# NPMDriver.net
KiCad netlist of a schematic drawn in EAGLE
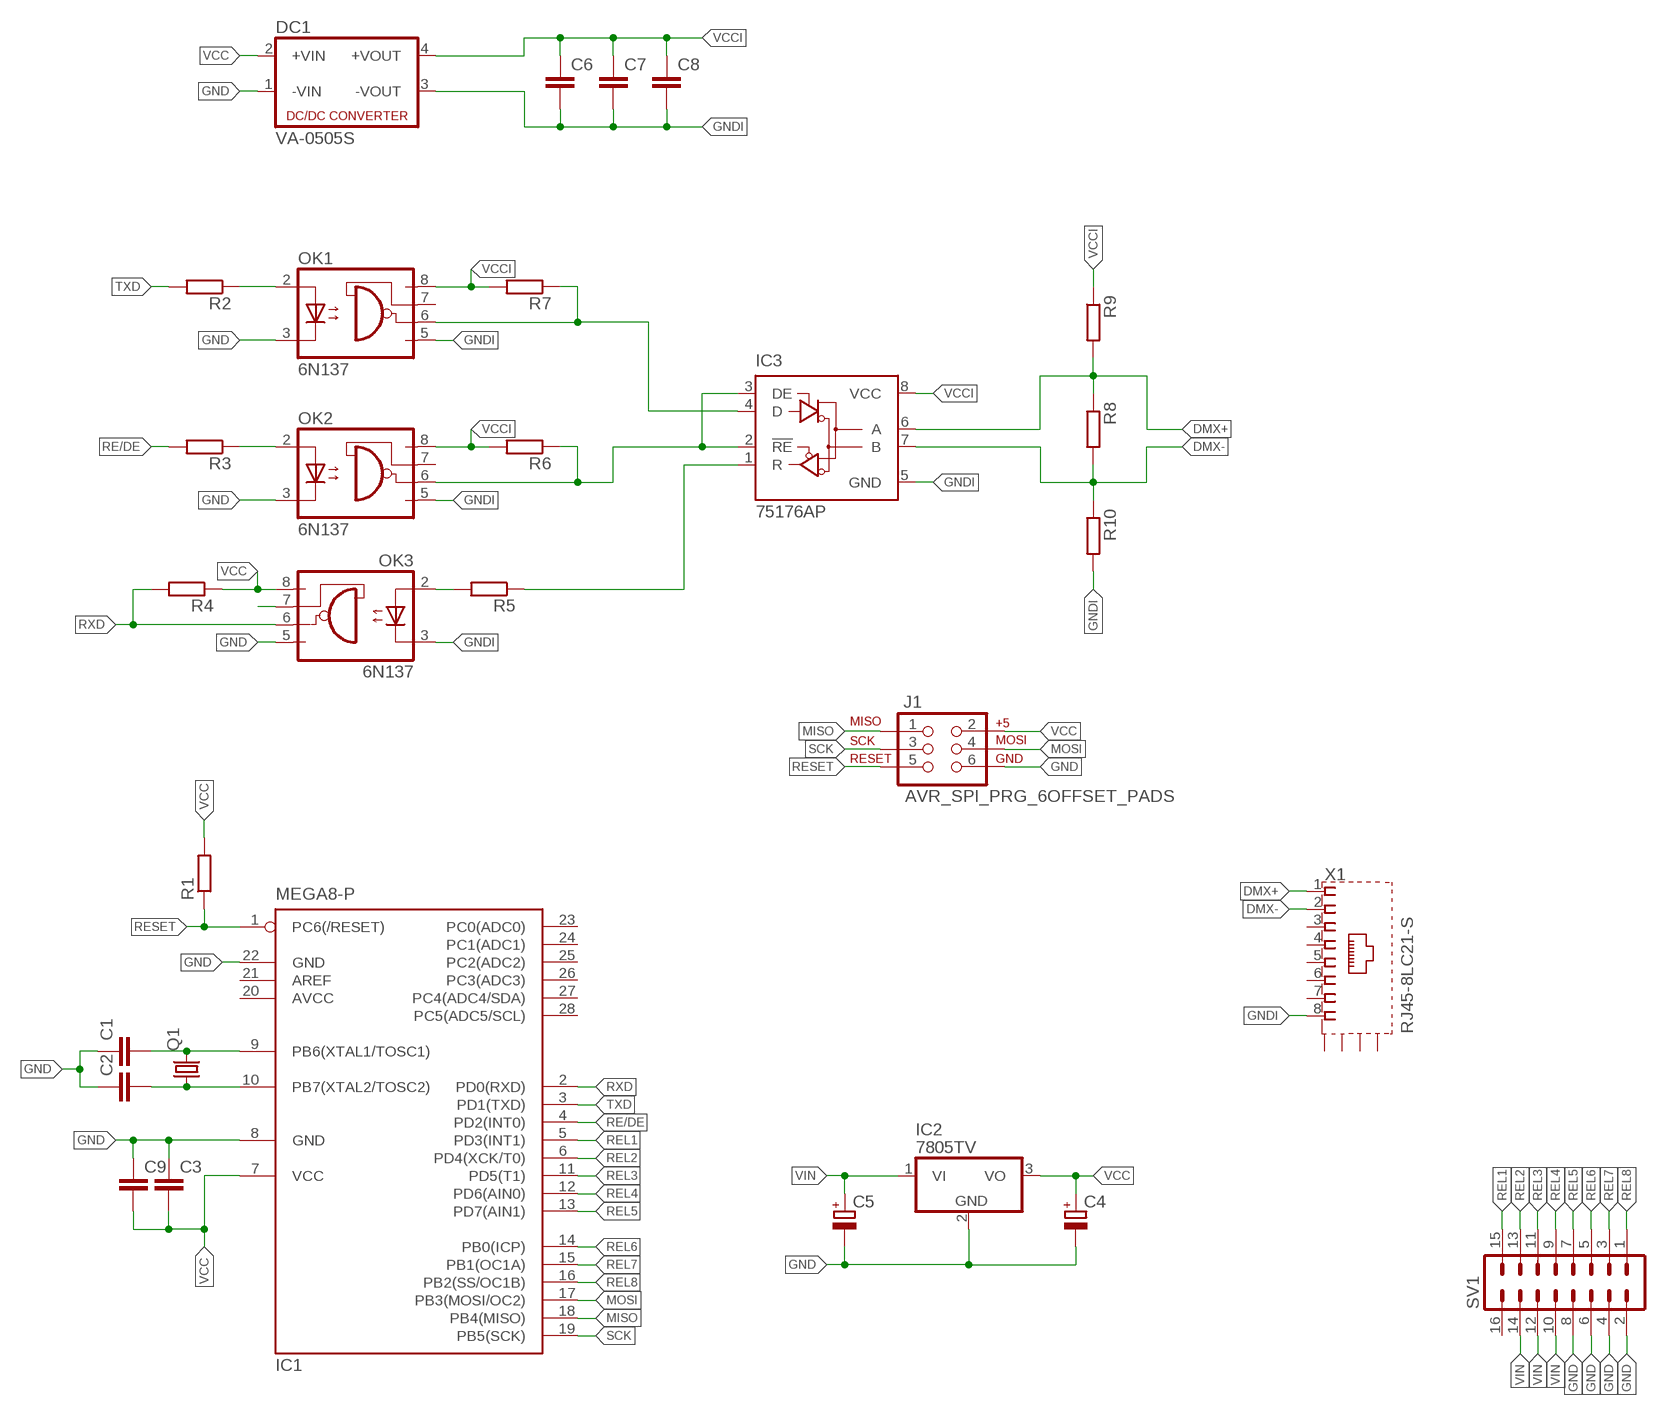
[diagram p0: schematic, sheet 1]

(export (version "E")
  (design (tool "Eeschema 10.0.6"))
  (components
    (comp (ref "C1")
      (value "C-EU025-025X050")
      (footprint "eagle-import:C025-025X050")
      (libsource (lib "eagle-import") (part "C-EU025-025X050"))
    )
    (comp (ref "C2")
      (value "C-EU025-025X050")
      (footprint "eagle-import:C025-025X050")
      (libsource (lib "eagle-import") (part "C-EU025-025X050"))
    )
    (comp (ref "C3")
      (value "C-EU050-035X075")
      (footprint "eagle-import:C050-035X075")
      (libsource (lib "eagle-import") (part "C-EU050-035X075"))
    )
    (comp (ref "C4")
      (value "CPOL-EUE5-8.5")
      (footprint "eagle-import:E5-8,5")
      (libsource (lib "eagle-import") (part "CPOL-EUE5-8.5"))
    )
    (comp (ref "C5")
      (value "CPOL-EUE5-8.5")
      (footprint "eagle-import:E5-8,5")
      (libsource (lib "eagle-import") (part "CPOL-EUE5-8.5"))
    )
    (comp (ref "C6")
      (value "C-EU050-035X075")
      (footprint "eagle-import:C050-035X075")
      (libsource (lib "eagle-import") (part "C-EU050-035X075"))
    )
    (comp (ref "C7")
      (value "C-EU050-035X075")
      (footprint "eagle-import:C050-035X075")
      (libsource (lib "eagle-import") (part "C-EU050-035X075"))
    )
    (comp (ref "C8")
      (value "C-EU050-035X075")
      (footprint "eagle-import:C050-035X075")
      (libsource (lib "eagle-import") (part "C-EU050-035X075"))
    )
    (comp (ref "C9")
      (value "C-EU050-035X075")
      (footprint "eagle-import:C050-035X075")
      (libsource (lib "eagle-import") (part "C-EU050-035X075"))
    )
    (comp (ref "DC1")
      (value "VA-0505S")
      (footprint "eagle-import:4SIL")
      (libsource (lib "eagle-import") (part "VA-?S0505"))
    )
    (comp (ref "IC1")
      (value "MEGA8-P")
      (footprint "eagle-import:DIL28-3")
      (libsource (lib "eagle-import") (part "MEGA8-P"))
    )
    (comp (ref "IC2")
      (value "7805TV")
      (footprint "eagle-import:TO220V")
      (libsource (lib "eagle-import") (part "78TV05"))
    )
    (comp (ref "IC3")
      (value "75176AP")
      (footprint "eagle-import:DIL08")
      (libsource (lib "eagle-import") (part "75176AP"))
    )
    (comp (ref "J1")
      (value "AVR_SPI_PRG_6OFFSET_PADS")
      (footprint "eagle-import:2X3_OFFSET")
      (libsource (lib "eagle-import") (part "AVR_SPI_PRG_6OFFSET_PADS"))
    )
    (comp (ref "OK1")
      (value "6N137")
      (footprint "eagle-import:DIL08")
      (libsource (lib "eagle-import") (part "6N137"))
    )
    (comp (ref "OK2")
      (value "6N137")
      (footprint "eagle-import:DIL08")
      (libsource (lib "eagle-import") (part "6N137"))
    )
    (comp (ref "OK3")
      (value "6N137")
      (footprint "eagle-import:DIL08")
      (libsource (lib "eagle-import") (part "6N137"))
    )
    (comp (ref "Q1")
      (value "CRYSTALHC49S")
      (footprint "eagle-import:HC49_S")
      (libsource (lib "eagle-import") (part "CRYSTALHC49S"))
    )
    (comp (ref "R1")
      (value "R-EU_0207/10")
      (footprint "eagle-import:0207_10")
      (libsource (lib "eagle-import") (part "R-EU_0207/10"))
    )
    (comp (ref "R2")
      (value "R-EU_0207/10")
      (footprint "eagle-import:0207_10")
      (libsource (lib "eagle-import") (part "R-EU_0207/10"))
    )
    (comp (ref "R3")
      (value "R-EU_0207/10")
      (footprint "eagle-import:0207_10")
      (libsource (lib "eagle-import") (part "R-EU_0207/10"))
    )
    (comp (ref "R4")
      (value "R-EU_0207/10")
      (footprint "eagle-import:0207_10")
      (libsource (lib "eagle-import") (part "R-EU_0207/10"))
    )
    (comp (ref "R5")
      (value "R-EU_0207/10")
      (footprint "eagle-import:0207_10")
      (libsource (lib "eagle-import") (part "R-EU_0207/10"))
    )
    (comp (ref "R6")
      (value "R-EU_0207/10")
      (footprint "eagle-import:0207_10")
      (libsource (lib "eagle-import") (part "R-EU_0207/10"))
    )
    (comp (ref "R7")
      (value "R-EU_0207/10")
      (footprint "eagle-import:0207_10")
      (libsource (lib "eagle-import") (part "R-EU_0207/10"))
    )
    (comp (ref "R8")
      (value "R-EU_0207/10")
      (footprint "eagle-import:0207_10")
      (libsource (lib "eagle-import") (part "R-EU_0207/10"))
    )
    (comp (ref "R9")
      (value "R-EU_0207/10")
      (footprint "eagle-import:0207_10")
      (libsource (lib "eagle-import") (part "R-EU_0207/10"))
    )
    (comp (ref "R10")
      (value "R-EU_0207/10")
      (footprint "eagle-import:0207_10")
      (libsource (lib "eagle-import") (part "R-EU_0207/10"))
    )
    (comp (ref "SV1")
      (value "ML163M")
      (footprint "eagle-import:3M_16")
      (libsource (lib "eagle-import") (part "ML163M"))
    )
    (comp (ref "X1")
      (value "RJ45-8LC21-S")
      (footprint "eagle-import:RJ45-SHIELD1")
      (libsource (lib "eagle-import") (part "RJ4521-S-8LC"))
    )
  )
  (nets
    (net (code "1") (name "/AVCC") (class "Default")
      (node (ref "IC1") (pin "20") (pinfunction "AVCC_20") (pintype "power_in"))
    )
    (net (code "2") (name "DMX+") (class "Default")
      (node (ref "IC3") (pin "6") (pinfunction "A_6") (pintype "output"))
      (node (ref "R8") (pin "1") (pinfunction "1_1") (pintype "passive"))
      (node (ref "R9") (pin "2") (pinfunction "2_2") (pintype "passive"))
      (node (ref "X1") (pin "1") (pinfunction "1_1") (pintype "passive"))
    )
    (net (code "3") (name "DMX-") (class "Default")
      (node (ref "IC3") (pin "7") (pinfunction "B_7") (pintype "output"))
      (node (ref "R10") (pin "1") (pinfunction "1_1") (pintype "passive"))
      (node (ref "R8") (pin "2") (pinfunction "2_2") (pintype "passive"))
      (node (ref "X1") (pin "2") (pinfunction "2_2") (pintype "passive"))
    )
    (net (code "4") (name "GND") (class "Default")
      (node (ref "C1") (pin "1") (pinfunction "1_1") (pintype "passive"))
      (node (ref "C2") (pin "1") (pinfunction "1_1") (pintype "passive"))
      (node (ref "C3") (pin "1") (pinfunction "1_1") (pintype "passive"))
      (node (ref "C4") (pin "-") (pinfunction "-_-") (pintype "passive"))
      (node (ref "C5") (pin "-") (pinfunction "-_-") (pintype "passive"))
      (node (ref "C9") (pin "1") (pinfunction "1_1") (pintype "passive"))
      (node (ref "DC1") (pin "1") (pinfunction "-VIN_1") (pintype "passive"))
      (node (ref "IC1") (pin "22") (pinfunction "GND_22") (pintype "power_in"))
      (node (ref "IC1") (pin "8") (pinfunction "GND_8") (pintype "power_in"))
      (node (ref "IC2") (pin "2") (pinfunction "GND_2") (pintype "passive"))
      (node (ref "J1") (pin "6") (pinfunction "6_6") (pintype "passive"))
      (node (ref "OK1") (pin "3") (pinfunction "C_3") (pintype "passive"))
      (node (ref "OK2") (pin "3") (pinfunction "C_3") (pintype "passive"))
      (node (ref "OK3") (pin "5") (pinfunction "GND_5") (pintype "passive"))
      (node (ref "SV1") (pin "2") (pinfunction "2_2") (pintype "passive"))
      (node (ref "SV1") (pin "4") (pinfunction "4_4") (pintype "passive"))
      (node (ref "SV1") (pin "6") (pinfunction "6_6") (pintype "passive"))
      (node (ref "SV1") (pin "8") (pinfunction "8_8") (pintype "passive"))
    )
    (net (code "5") (name "GNDI") (class "Default")
      (node (ref "C6") (pin "2") (pinfunction "2_2") (pintype "passive"))
      (node (ref "C7") (pin "2") (pinfunction "2_2") (pintype "passive"))
      (node (ref "C8") (pin "2") (pinfunction "2_2") (pintype "passive"))
      (node (ref "DC1") (pin "3") (pinfunction "-VOUT_3") (pintype "passive"))
      (node (ref "IC3") (pin "5") (pinfunction "GND_5") (pintype "power_in"))
      (node (ref "OK1") (pin "5") (pinfunction "GND_5") (pintype "passive"))
      (node (ref "OK2") (pin "5") (pinfunction "GND_5") (pintype "passive"))
      (node (ref "OK3") (pin "3") (pinfunction "C_3") (pintype "passive"))
      (node (ref "R10") (pin "2") (pinfunction "2_2") (pintype "passive"))
      (node (ref "X1") (pin "8") (pinfunction "8_8") (pintype "passive"))
    )
    (net (code "6") (name "MISO") (class "Default")
      (node (ref "IC1") (pin "18") (pinfunction "PB4(MISO)_18") (pintype "bidirectional"))
      (node (ref "J1") (pin "1") (pinfunction "1_1") (pintype "passive"))
    )
    (net (code "7") (name "MOSI") (class "Default")
      (node (ref "IC1") (pin "17") (pinfunction "PB3(MOSI/OC2)_17") (pintype "bidirectional"))
      (node (ref "J1") (pin "4") (pinfunction "4_4") (pintype "passive"))
    )
    (net (code "8") (name "Net-(IC1-PB6(XTAL1{slash}TOSC1))") (class "Default")
      (node (ref "C1") (pin "2") (pinfunction "2_2") (pintype "passive"))
      (node (ref "IC1") (pin "9") (pinfunction "PB6(XTAL1/TOSC1)_9") (pintype "bidirectional"))
      (node (ref "Q1") (pin "2") (pinfunction "2_2") (pintype "passive"))
    )
    (net (code "9") (name "Net-(IC1-PB7(XTAL2{slash}TOSC2))") (class "Default")
      (node (ref "C2") (pin "2") (pinfunction "2_2") (pintype "passive"))
      (node (ref "IC1") (pin "10") (pinfunction "PB7(XTAL2/TOSC2)_10") (pintype "bidirectional"))
      (node (ref "Q1") (pin "1") (pinfunction "1_1") (pintype "passive"))
    )
    (net (code "10") (name "Net-(IC3-D)") (class "Default")
      (node (ref "IC3") (pin "4") (pinfunction "D_4") (pintype "input"))
      (node (ref "OK1") (pin "6") (pinfunction "VO_6") (pintype "passive"))
      (node (ref "R7") (pin "1") (pinfunction "1_1") (pintype "passive"))
    )
    (net (code "11") (name "Net-(IC3-DE)") (class "Default")
      (node (ref "IC3") (pin "2") (pinfunction "~{RE}_2") (pintype "input"))
      (node (ref "IC3") (pin "3") (pinfunction "DE_3") (pintype "input"))
      (node (ref "OK2") (pin "6") (pinfunction "VO_6") (pintype "passive"))
      (node (ref "R6") (pin "1") (pinfunction "1_1") (pintype "passive"))
    )
    (net (code "12") (name "Net-(IC3-R)") (class "Default")
      (node (ref "IC3") (pin "1") (pinfunction "R_1") (pintype "input"))
      (node (ref "R5") (pin "1") (pinfunction "1_1") (pintype "passive"))
    )
    (net (code "13") (name "Net-(OK1-A)") (class "Default")
      (node (ref "OK1") (pin "2") (pinfunction "A_2") (pintype "passive"))
      (node (ref "R2") (pin "1") (pinfunction "1_1") (pintype "passive"))
    )
    (net (code "14") (name "Net-(OK2-A)") (class "Default")
      (node (ref "OK2") (pin "2") (pinfunction "A_2") (pintype "passive"))
      (node (ref "R3") (pin "1") (pinfunction "1_1") (pintype "passive"))
    )
    (net (code "15") (name "Net-(OK3-A)") (class "Default")
      (node (ref "OK3") (pin "2") (pinfunction "A_2") (pintype "passive"))
      (node (ref "R5") (pin "2") (pinfunction "2_2") (pintype "passive"))
    )
    (net (code "16") (name "REL1") (class "Default")
      (node (ref "IC1") (pin "5") (pinfunction "PD3(INT1)_5") (pintype "bidirectional"))
      (node (ref "SV1") (pin "15") (pinfunction "15_15") (pintype "passive"))
    )
    (net (code "17") (name "REL2") (class "Default")
      (node (ref "IC1") (pin "6") (pinfunction "PD4(XCK/T0)_6") (pintype "bidirectional"))
      (node (ref "SV1") (pin "13") (pinfunction "13_13") (pintype "passive"))
    )
    (net (code "18") (name "REL3") (class "Default")
      (node (ref "IC1") (pin "11") (pinfunction "PD5(T1)_11") (pintype "bidirectional"))
      (node (ref "SV1") (pin "11") (pinfunction "11_11") (pintype "passive"))
    )
    (net (code "19") (name "REL4") (class "Default")
      (node (ref "IC1") (pin "12") (pinfunction "PD6(AIN0)_12") (pintype "bidirectional"))
      (node (ref "SV1") (pin "9") (pinfunction "9_9") (pintype "passive"))
    )
    (net (code "20") (name "REL5") (class "Default")
      (node (ref "IC1") (pin "13") (pinfunction "PD7(AIN1)_13") (pintype "bidirectional"))
      (node (ref "SV1") (pin "7") (pinfunction "7_7") (pintype "passive"))
    )
    (net (code "21") (name "REL6") (class "Default")
      (node (ref "IC1") (pin "14") (pinfunction "PB0(ICP)_14") (pintype "bidirectional"))
      (node (ref "SV1") (pin "5") (pinfunction "5_5") (pintype "passive"))
    )
    (net (code "22") (name "REL7") (class "Default")
      (node (ref "IC1") (pin "15") (pinfunction "PB1(OC1A)_15") (pintype "bidirectional"))
      (node (ref "SV1") (pin "3") (pinfunction "3_3") (pintype "passive"))
    )
    (net (code "23") (name "REL8") (class "Default")
      (node (ref "IC1") (pin "16") (pinfunction "PB2(SS/OC1B)_16") (pintype "bidirectional"))
      (node (ref "SV1") (pin "1") (pinfunction "1_1") (pintype "passive"))
    )
    (net (code "24") (name "RESET") (class "Default")
      (node (ref "IC1") (pin "1") (pinfunction "PC6(/RESET)_1") (pintype "bidirectional"))
      (node (ref "J1") (pin "5") (pinfunction "5_5") (pintype "passive"))
      (node (ref "R1") (pin "1") (pinfunction "1_1") (pintype "passive"))
    )
    (net (code "25") (name "RE{slash}DE") (class "Default")
      (node (ref "IC1") (pin "4") (pinfunction "PD2(INT0)_4") (pintype "bidirectional"))
      (node (ref "R3") (pin "2") (pinfunction "2_2") (pintype "passive"))
    )
    (net (code "26") (name "RXD") (class "Default")
      (node (ref "IC1") (pin "2") (pinfunction "PD0(RXD)_2") (pintype "bidirectional"))
      (node (ref "OK3") (pin "6") (pinfunction "VO_6") (pintype "passive"))
      (node (ref "R4") (pin "2") (pinfunction "2_2") (pintype "passive"))
    )
    (net (code "27") (name "SCK") (class "Default")
      (node (ref "IC1") (pin "19") (pinfunction "PB5(SCK)_19") (pintype "bidirectional"))
      (node (ref "J1") (pin "3") (pinfunction "3_3") (pintype "passive"))
    )
    (net (code "28") (name "TXD") (class "Default")
      (node (ref "IC1") (pin "3") (pinfunction "PD1(TXD)_3") (pintype "bidirectional"))
      (node (ref "R2") (pin "2") (pinfunction "2_2") (pintype "passive"))
    )
    (net (code "29") (name "VCC") (class "Default")
      (node (ref "C3") (pin "2") (pinfunction "2_2") (pintype "passive"))
      (node (ref "C4") (pin "+") (pinfunction "+_+") (pintype "passive"))
      (node (ref "C9") (pin "2") (pinfunction "2_2") (pintype "passive"))
      (node (ref "DC1") (pin "2") (pinfunction "+VIN_2") (pintype "passive"))
      (node (ref "IC1") (pin "7") (pinfunction "VCC_7") (pintype "power_in"))
      (node (ref "IC2") (pin "3") (pinfunction "VO_3") (pintype "passive"))
      (node (ref "J1") (pin "2") (pinfunction "2_2") (pintype "passive"))
      (node (ref "OK3") (pin "8") (pinfunction "VCC_8") (pintype "passive"))
      (node (ref "R1") (pin "2") (pinfunction "2_2") (pintype "passive"))
      (node (ref "R4") (pin "1") (pinfunction "1_1") (pintype "passive"))
    )
    (net (code "30") (name "VCCI") (class "Default")
      (node (ref "C6") (pin "1") (pinfunction "1_1") (pintype "passive"))
      (node (ref "C7") (pin "1") (pinfunction "1_1") (pintype "passive"))
      (node (ref "C8") (pin "1") (pinfunction "1_1") (pintype "passive"))
      (node (ref "DC1") (pin "4") (pinfunction "+VOUT_4") (pintype "passive"))
      (node (ref "IC3") (pin "8") (pinfunction "VCC_8") (pintype "power_in"))
      (node (ref "OK1") (pin "8") (pinfunction "VCC_8") (pintype "passive"))
      (node (ref "OK2") (pin "8") (pinfunction "VCC_8") (pintype "passive"))
      (node (ref "R6") (pin "2") (pinfunction "2_2") (pintype "passive"))
      (node (ref "R7") (pin "2") (pinfunction "2_2") (pintype "passive"))
      (node (ref "R9") (pin "1") (pinfunction "1_1") (pintype "passive"))
    )
    (net (code "31") (name "VIN") (class "Default")
      (node (ref "C5") (pin "+") (pinfunction "+_+") (pintype "passive"))
      (node (ref "IC2") (pin "1") (pinfunction "VI_1") (pintype "input"))
      (node (ref "SV1") (pin "10") (pinfunction "10_10") (pintype "passive"))
      (node (ref "SV1") (pin "12") (pinfunction "12_12") (pintype "passive"))
      (node (ref "SV1") (pin "14") (pinfunction "14_14") (pintype "passive"))
    )
    (net (code "32") (name "unconnected-(IC1-AREF-Pad21)") (class "Default")
      (node (ref "IC1") (pin "21") (pinfunction "AREF_21") (pintype "passive"))
    )
    (net (code "33") (name "unconnected-(IC1-PC0(ADC0)-Pad23)") (class "Default")
      (node (ref "IC1") (pin "23") (pinfunction "PC0(ADC0)_23") (pintype "bidirectional"))
    )
    (net (code "34") (name "unconnected-(IC1-PC1(ADC1)-Pad24)") (class "Default")
      (node (ref "IC1") (pin "24") (pinfunction "PC1(ADC1)_24") (pintype "bidirectional"))
    )
    (net (code "35") (name "unconnected-(IC1-PC2(ADC2)-Pad25)") (class "Default")
      (node (ref "IC1") (pin "25") (pinfunction "PC2(ADC2)_25") (pintype "bidirectional"))
    )
    (net (code "36") (name "unconnected-(IC1-PC3(ADC3)-Pad26)") (class "Default")
      (node (ref "IC1") (pin "26") (pinfunction "PC3(ADC3)_26") (pintype "bidirectional"))
    )
    (net (code "37") (name "unconnected-(IC1-PC4(ADC4{slash}SDA)-Pad27)") (class "Default")
      (node (ref "IC1") (pin "27") (pinfunction "PC4(ADC4/SDA)_27") (pintype "bidirectional"))
    )
    (net (code "38") (name "unconnected-(IC1-PC5(ADC5{slash}SCL)-Pad28)") (class "Default")
      (node (ref "IC1") (pin "28") (pinfunction "PC5(ADC5/SCL)_28") (pintype "bidirectional"))
    )
    (net (code "39") (name "unconnected-(OK1-VE-Pad7)") (class "Default")
      (node (ref "OK1") (pin "7") (pinfunction "VE_7") (pintype "passive"))
    )
    (net (code "40") (name "unconnected-(OK2-VE-Pad7)") (class "Default")
      (node (ref "OK2") (pin "7") (pinfunction "VE_7") (pintype "passive"))
    )
    (net (code "41") (name "unconnected-(OK3-VE-Pad7)") (class "Default")
      (node (ref "OK3") (pin "7") (pinfunction "VE_7") (pintype "passive"))
    )
    (net (code "42") (name "unconnected-(SV1-Pad16)") (class "Default")
      (node (ref "SV1") (pin "16") (pinfunction "16_16") (pintype "passive"))
    )
    (net (code "43") (name "unconnected-(X1-Pad3)") (class "Default")
      (node (ref "X1") (pin "3") (pinfunction "3_3") (pintype "passive"))
    )
    (net (code "44") (name "unconnected-(X1-Pad4)") (class "Default")
      (node (ref "X1") (pin "4") (pinfunction "4_4") (pintype "passive"))
    )
    (net (code "45") (name "unconnected-(X1-Pad5)") (class "Default")
      (node (ref "X1") (pin "5") (pinfunction "5_5") (pintype "passive"))
    )
    (net (code "46") (name "unconnected-(X1-Pad6)") (class "Default")
      (node (ref "X1") (pin "6") (pinfunction "6_6") (pintype "passive"))
    )
    (net (code "47") (name "unconnected-(X1-Pad7)") (class "Default")
      (node (ref "X1") (pin "7") (pinfunction "7_7") (pintype "passive"))
    )
    (net (code "48") (name "unconnected-(X1-S-PadS1)") (class "Default")
      (node (ref "X1") (pin "S1") (pinfunction "S_S1") (pintype "passive"))
    )
    (net (code "49") (name "unconnected-(X1-S-PadS2)") (class "Default")
      (node (ref "X1") (pin "S2") (pinfunction "S_S2") (pintype "passive"))
    )
    (net (code "50") (name "unconnected-(X1-S-PadS3)") (class "Default")
      (node (ref "X1") (pin "S3") (pinfunction "S_S3") (pintype "passive"))
    )
    (net (code "51") (name "unconnected-(X1-S-PadS4)") (class "Default")
      (node (ref "X1") (pin "S4") (pinfunction "S_S4") (pintype "passive"))
    )
  )
)
